# CurrentS_2.net
KiCad netlist of a schematic drawn in Altium Designer
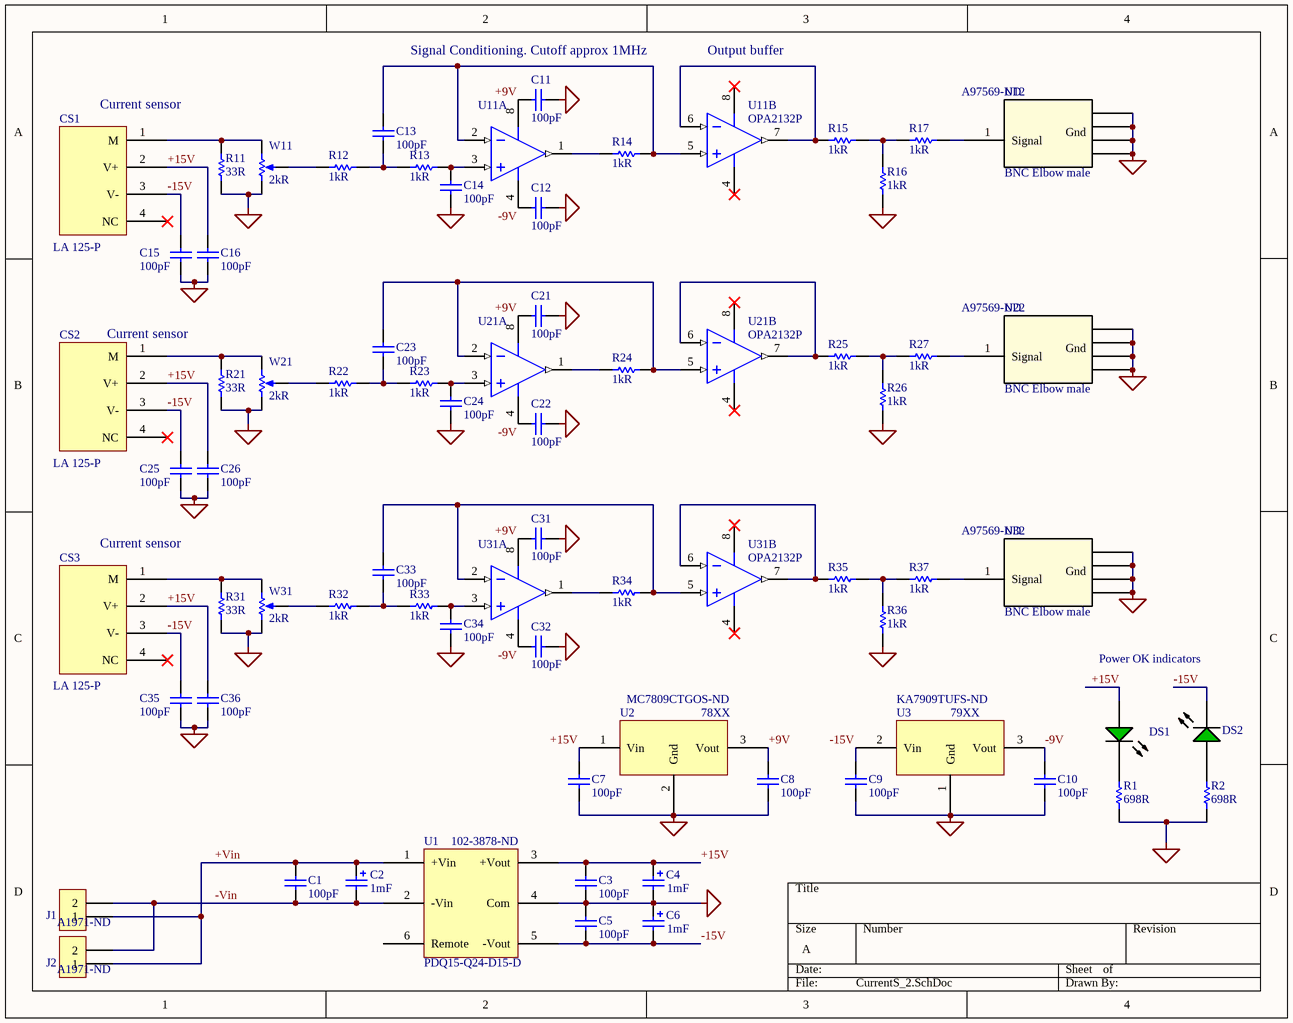
[diagram p0: CurrentS_2.SchDoc]

(export (version "E")
  (design (tool "Eeschema 10.0.6"))
  (components
    (comp (ref "C1")
      (value "C3216C0G2J101J060AA")
      (footprint "C1206")
      (fields
        (field (name "MANUFACTURER") "TDK")
        (field (name "TOLERANCE") "5%")
        (field (name "VOLTAGE") "630V")
        (field (name "CAPACITANCE") "100pF")
      )
      (libsource (lib "KyleCustomModels") (part "C3216C0G2J101J060AA"))
    )
    (comp (ref "C2")
      (value "ESMG500ELL102MK25S")
      (footprint "CAP.2/.5")
      (description "CAP ALUM 1000UF 20% 50V RADIAL")
      (fields
        (field (name "MANUFACTURER") "United Chemi-Con")
        (field (name "TOLERANCE") "20%")
        (field (name "CAPACITANCE") "1mF")
      )
      (libsource (lib "KyleCustomModels") (part "ESMG500ELL102MK25S"))
    )
    (comp (ref "C3")
      (value "C3216C0G2J101J060AA")
      (footprint "C1206")
      (fields
        (field (name "MANUFACTURER") "TDK")
        (field (name "TOLERANCE") "5%")
        (field (name "VOLTAGE") "630V")
        (field (name "CAPACITANCE") "100pF")
      )
      (libsource (lib "KyleCustomModels") (part "C3216C0G2J101J060AA"))
    )
    (comp (ref "C4")
      (value "ESMG500ELL102MK25S")
      (footprint "CAP.2/.5")
      (description "CAP ALUM 1000UF 20% 50V RADIAL")
      (fields
        (field (name "MANUFACTURER") "United Chemi-Con")
        (field (name "TOLERANCE") "20%")
        (field (name "CAPACITANCE") "1mF")
      )
      (libsource (lib "KyleCustomModels") (part "ESMG500ELL102MK25S"))
    )
    (comp (ref "C5")
      (value "C3216C0G2J101J060AA")
      (footprint "C1206")
      (fields
        (field (name "MANUFACTURER") "TDK")
        (field (name "TOLERANCE") "5%")
        (field (name "VOLTAGE") "630V")
        (field (name "CAPACITANCE") "100pF")
      )
      (libsource (lib "KyleCustomModels") (part "C3216C0G2J101J060AA"))
    )
    (comp (ref "C6")
      (value "ESMG500ELL102MK25S")
      (footprint "CAP.2/.5")
      (description "CAP ALUM 1000UF 20% 50V RADIAL")
      (fields
        (field (name "MANUFACTURER") "United Chemi-Con")
        (field (name "TOLERANCE") "20%")
        (field (name "CAPACITANCE") "1mF")
      )
      (libsource (lib "KyleCustomModels") (part "ESMG500ELL102MK25S"))
    )
    (comp (ref "C7")
      (value "C3216C0G2J101J060AA")
      (footprint "C1206")
      (fields
        (field (name "MANUFACTURER") "TDK")
        (field (name "TOLERANCE") "5%")
        (field (name "VOLTAGE") "630V")
        (field (name "CAPACITANCE") "100pF")
      )
      (libsource (lib "KyleCustomModels") (part "C3216C0G2J101J060AA"))
    )
    (comp (ref "C8")
      (value "C3216C0G2J101J060AA")
      (footprint "C1206")
      (fields
        (field (name "MANUFACTURER") "TDK")
        (field (name "TOLERANCE") "5%")
        (field (name "VOLTAGE") "630V")
        (field (name "CAPACITANCE") "100pF")
      )
      (libsource (lib "KyleCustomModels") (part "C3216C0G2J101J060AA"))
    )
    (comp (ref "C9")
      (value "C3216C0G2J101J060AA")
      (footprint "C1206")
      (fields
        (field (name "MANUFACTURER") "TDK")
        (field (name "TOLERANCE") "5%")
        (field (name "VOLTAGE") "630V")
        (field (name "CAPACITANCE") "100pF")
      )
      (libsource (lib "KyleCustomModels") (part "C3216C0G2J101J060AA"))
    )
    (comp (ref "C10")
      (value "C3216C0G2J101J060AA")
      (footprint "C1206")
      (fields
        (field (name "MANUFACTURER") "TDK")
        (field (name "TOLERANCE") "5%")
        (field (name "VOLTAGE") "630V")
        (field (name "CAPACITANCE") "100pF")
      )
      (libsource (lib "KyleCustomModels") (part "C3216C0G2J101J060AA"))
    )
    (comp (ref "C11")
      (value "C3216C0G2J101J060AA")
      (footprint "C1206")
      (fields
        (field (name "MANUFACTURER") "TDK")
        (field (name "TOLERANCE") "5%")
        (field (name "VOLTAGE") "630V")
        (field (name "CAPACITANCE") "100pF")
      )
      (libsource (lib "KyleCustomModels") (part "C3216C0G2J101J060AA"))
    )
    (comp (ref "C12")
      (value "C3216C0G2J101J060AA")
      (footprint "C1206")
      (fields
        (field (name "MANUFACTURER") "TDK")
        (field (name "TOLERANCE") "5%")
        (field (name "VOLTAGE") "630V")
        (field (name "CAPACITANCE") "100pF")
      )
      (libsource (lib "KyleCustomModels") (part "C3216C0G2J101J060AA"))
    )
    (comp (ref "C13")
      (value "C3216C0G2J101J060AA")
      (footprint "C1206")
      (fields
        (field (name "MANUFACTURER") "TDK")
        (field (name "TOLERANCE") "5%")
        (field (name "VOLTAGE") "630V")
        (field (name "CAPACITANCE") "100pF")
      )
      (libsource (lib "KyleCustomModels") (part "C3216C0G2J101J060AA"))
    )
    (comp (ref "C14")
      (value "C3216C0G2J101J060AA")
      (footprint "C1206")
      (fields
        (field (name "MANUFACTURER") "TDK")
        (field (name "TOLERANCE") "5%")
        (field (name "VOLTAGE") "630V")
        (field (name "CAPACITANCE") "100pF")
      )
      (libsource (lib "KyleCustomModels") (part "C3216C0G2J101J060AA"))
    )
    (comp (ref "C15")
      (value "C3216C0G2J101J060AA")
      (footprint "C1206")
      (fields
        (field (name "MANUFACTURER") "TDK")
        (field (name "TOLERANCE") "5%")
        (field (name "VOLTAGE") "630V")
        (field (name "CAPACITANCE") "100pF")
      )
      (libsource (lib "KyleCustomModels") (part "C3216C0G2J101J060AA"))
    )
    (comp (ref "C16")
      (value "C3216C0G2J101J060AA")
      (footprint "C1206")
      (fields
        (field (name "MANUFACTURER") "TDK")
        (field (name "TOLERANCE") "5%")
        (field (name "VOLTAGE") "630V")
        (field (name "CAPACITANCE") "100pF")
      )
      (libsource (lib "KyleCustomModels") (part "C3216C0G2J101J060AA"))
    )
    (comp (ref "C21")
      (value "C3216C0G2J101J060AA")
      (footprint "C1206")
      (fields
        (field (name "MANUFACTURER") "TDK")
        (field (name "TOLERANCE") "5%")
        (field (name "VOLTAGE") "630V")
        (field (name "CAPACITANCE") "100pF")
      )
      (libsource (lib "KyleCustomModels") (part "C3216C0G2J101J060AA"))
    )
    (comp (ref "C22")
      (value "C3216C0G2J101J060AA")
      (footprint "C1206")
      (fields
        (field (name "MANUFACTURER") "TDK")
        (field (name "TOLERANCE") "5%")
        (field (name "VOLTAGE") "630V")
        (field (name "CAPACITANCE") "100pF")
      )
      (libsource (lib "KyleCustomModels") (part "C3216C0G2J101J060AA"))
    )
    (comp (ref "C23")
      (value "C3216C0G2J101J060AA")
      (footprint "C1206")
      (fields
        (field (name "MANUFACTURER") "TDK")
        (field (name "TOLERANCE") "5%")
        (field (name "VOLTAGE") "630V")
        (field (name "CAPACITANCE") "100pF")
      )
      (libsource (lib "KyleCustomModels") (part "C3216C0G2J101J060AA"))
    )
    (comp (ref "C24")
      (value "C3216C0G2J101J060AA")
      (footprint "C1206")
      (fields
        (field (name "MANUFACTURER") "TDK")
        (field (name "TOLERANCE") "5%")
        (field (name "VOLTAGE") "630V")
        (field (name "CAPACITANCE") "100pF")
      )
      (libsource (lib "KyleCustomModels") (part "C3216C0G2J101J060AA"))
    )
    (comp (ref "C25")
      (value "C3216C0G2J101J060AA")
      (footprint "C1206")
      (fields
        (field (name "MANUFACTURER") "TDK")
        (field (name "TOLERANCE") "5%")
        (field (name "VOLTAGE") "630V")
        (field (name "CAPACITANCE") "100pF")
      )
      (libsource (lib "KyleCustomModels") (part "C3216C0G2J101J060AA"))
    )
    (comp (ref "C26")
      (value "C3216C0G2J101J060AA")
      (footprint "C1206")
      (fields
        (field (name "MANUFACTURER") "TDK")
        (field (name "TOLERANCE") "5%")
        (field (name "VOLTAGE") "630V")
        (field (name "CAPACITANCE") "100pF")
      )
      (libsource (lib "KyleCustomModels") (part "C3216C0G2J101J060AA"))
    )
    (comp (ref "C31")
      (value "C3216C0G2J101J060AA")
      (footprint "C1206")
      (fields
        (field (name "MANUFACTURER") "TDK")
        (field (name "TOLERANCE") "5%")
        (field (name "VOLTAGE") "630V")
        (field (name "CAPACITANCE") "100pF")
      )
      (libsource (lib "KyleCustomModels") (part "C3216C0G2J101J060AA"))
    )
    (comp (ref "C32")
      (value "C3216C0G2J101J060AA")
      (footprint "C1206")
      (fields
        (field (name "MANUFACTURER") "TDK")
        (field (name "TOLERANCE") "5%")
        (field (name "VOLTAGE") "630V")
        (field (name "CAPACITANCE") "100pF")
      )
      (libsource (lib "KyleCustomModels") (part "C3216C0G2J101J060AA"))
    )
    (comp (ref "C33")
      (value "C3216C0G2J101J060AA")
      (footprint "C1206")
      (fields
        (field (name "MANUFACTURER") "TDK")
        (field (name "TOLERANCE") "5%")
        (field (name "VOLTAGE") "630V")
        (field (name "CAPACITANCE") "100pF")
      )
      (libsource (lib "KyleCustomModels") (part "C3216C0G2J101J060AA"))
    )
    (comp (ref "C34")
      (value "C3216C0G2J101J060AA")
      (footprint "C1206")
      (fields
        (field (name "MANUFACTURER") "TDK")
        (field (name "TOLERANCE") "5%")
        (field (name "VOLTAGE") "630V")
        (field (name "CAPACITANCE") "100pF")
      )
      (libsource (lib "KyleCustomModels") (part "C3216C0G2J101J060AA"))
    )
    (comp (ref "C35")
      (value "C3216C0G2J101J060AA")
      (footprint "C1206")
      (fields
        (field (name "MANUFACTURER") "TDK")
        (field (name "TOLERANCE") "5%")
        (field (name "VOLTAGE") "630V")
        (field (name "CAPACITANCE") "100pF")
      )
      (libsource (lib "KyleCustomModels") (part "C3216C0G2J101J060AA"))
    )
    (comp (ref "C36")
      (value "C3216C0G2J101J060AA")
      (footprint "C1206")
      (fields
        (field (name "MANUFACTURER") "TDK")
        (field (name "TOLERANCE") "5%")
        (field (name "VOLTAGE") "630V")
        (field (name "CAPACITANCE") "100pF")
      )
      (libsource (lib "KyleCustomModels") (part "C3216C0G2J101J060AA"))
    )
    (comp (ref "CS1")
      (value "LA 125-P")
      (footprint "LA 125-P")
      (description "Hall-effect current transducer from LEM")
      (fields (field (name "MANUFACTURER") "LEM") (field (name "MANUFACTURER PART NUMBER") "LA125-P"))
      (libsource (lib "KyleCustomModels") (part "LA 125-P"))
    )
    (comp (ref "CS2")
      (value "LA 125-P")
      (footprint "LA 125-P")
      (description "Hall-effect current transducer from LEM")
      (fields (field (name "MANUFACTURER") "LEM") (field (name "MANUFACTURER PART NUMBER") "LA125-P"))
      (libsource (lib "KyleCustomModels") (part "LA 125-P"))
    )
    (comp (ref "CS3")
      (value "LA 125-P")
      (footprint "LA 125-P")
      (description "Hall-effect current transducer from LEM")
      (fields (field (name "MANUFACTURER") "LEM") (field (name "MANUFACTURER PART NUMBER") "LA125-P"))
      (libsource (lib "KyleCustomModels") (part "LA 125-P"))
    )
    (comp (ref "DS1")
      (value "SML-LXT0805GW-TR")
      (footprint "LUMX-SML-LXT0805_V")
      (description "LED, GREEN, 565 nm, 2 V, -25 to 80 degC, 2-Pin SMD, RoHS, Tape and Reel")
      (libsource (lib "Altium Content Vault") (part "LED-GREEN-AK-2"))
    )
    (comp (ref "DS2")
      (value "SML-LXT0805GW-TR")
      (footprint "LUMX-SML-LXT0805_V")
      (description "LED, GREEN, 565 nm, 2 V, -25 to 80 degC, 2-Pin SMD, RoHS, Tape and Reel")
      (libsource (lib "Altium Content Vault") (part "LED-GREEN-AK-2"))
    )
    (comp (ref "J1")
      (value "CON2")
      (footprint "3100-8-102-01")
      (description "Connector")
      (fields
        (field (name "MANUFACTURER") "TE Connectivity")
        (field (name "MANUFACTURER PART NUMBER") "640445-2")
        (field (name "SUPPLIER PART NUMBER 1") "A1971-ND")
      )
      (libsource (lib "ERL_Components") (part "CON2"))
    )
    (comp (ref "J2")
      (value "CON2")
      (footprint "3100-8-102-01")
      (description "Connector")
      (fields
        (field (name "MANUFACTURER") "TE Connectivity")
        (field (name "MANUFACTURER PART NUMBER") "640445-2")
        (field (name "SUPPLIER PART NUMBER 1") "A1971-ND")
      )
      (libsource (lib "ERL_Components") (part "CON2"))
    )
    (comp (ref "R1")
      (value "RC0805FR-07698RL")
      (footprint "R0805")
      (description "RES SMD 698 OHM 1% 1/8W 0805")
      (fields
        (field (name "MANUFACTURER") "Yageo")
        (field (name "TOLERANCE") "1%")
        (field (name "RESISTANCE") "698R")
      )
      (libsource (lib "KyleCustomModels") (part "RC0805FR-07698RL"))
    )
    (comp (ref "R2")
      (value "RC0805FR-07698RL")
      (footprint "R0805")
      (description "RES SMD 698 OHM 1% 1/8W 0805")
      (fields
        (field (name "MANUFACTURER") "Yageo")
        (field (name "TOLERANCE") "1%")
        (field (name "RESISTANCE") "698R")
      )
      (libsource (lib "KyleCustomModels") (part "RC0805FR-07698RL"))
    )
    (comp (ref "R11")
      (value "RC0805JR-0733RL")
      (footprint "R0805")
      (fields
        (field (name "MANUFACTURER") "Yageo")
        (field (name "TOLERANCE") "5%")
        (field (name "RESISTANCE") "33R")
      )
      (libsource (lib "KyleCustomModels") (part "RC0805JR-0733RL"))
    )
    (comp (ref "R12")
      (value "RC0805FR-071KL")
      (footprint "R0805")
      (description "RES SMD 1K OHM 1% 1/8W 0805")
      (fields
        (field (name "MANUFACTURER") "Yageo")
        (field (name "TOLERANCE") "1%")
        (field (name "RESISTANCE") "1kR")
      )
      (libsource (lib "KyleCustomModels") (part "RC0805FR-071KL"))
    )
    (comp (ref "R13")
      (value "RC0805FR-071KL")
      (footprint "R0805")
      (description "RES SMD 1K OHM 1% 1/8W 0805")
      (fields
        (field (name "MANUFACTURER") "Yageo")
        (field (name "TOLERANCE") "1%")
        (field (name "RESISTANCE") "1kR")
      )
      (libsource (lib "KyleCustomModels") (part "RC0805FR-071KL"))
    )
    (comp (ref "R14")
      (value "RC0805FR-071KL")
      (footprint "R0805")
      (description "RES SMD 1K OHM 1% 1/8W 0805")
      (fields
        (field (name "MANUFACTURER") "Yageo")
        (field (name "TOLERANCE") "1%")
        (field (name "RESISTANCE") "1kR")
      )
      (libsource (lib "KyleCustomModels") (part "RC0805FR-071KL"))
    )
    (comp (ref "R15")
      (value "RC0805FR-071KL")
      (footprint "R0805")
      (description "RES SMD 1K OHM 1% 1/8W 0805")
      (fields
        (field (name "MANUFACTURER") "Yageo")
        (field (name "TOLERANCE") "1%")
        (field (name "RESISTANCE") "1kR")
      )
      (libsource (lib "KyleCustomModels") (part "RC0805FR-071KL"))
    )
    (comp (ref "R16")
      (value "RC0805FR-071KL")
      (footprint "R0805")
      (description "RES SMD 1K OHM 1% 1/8W 0805")
      (fields
        (field (name "MANUFACTURER") "Yageo")
        (field (name "TOLERANCE") "1%")
        (field (name "RESISTANCE") "1kR")
      )
      (libsource (lib "KyleCustomModels") (part "RC0805FR-071KL"))
    )
    (comp (ref "R17")
      (value "RC0805FR-071KL")
      (footprint "R0805")
      (description "RES SMD 1K OHM 1% 1/8W 0805")
      (fields
        (field (name "MANUFACTURER") "Yageo")
        (field (name "TOLERANCE") "1%")
        (field (name "RESISTANCE") "1kR")
      )
      (libsource (lib "KyleCustomModels") (part "RC0805FR-071KL"))
    )
    (comp (ref "R21")
      (value "RC0805JR-0733RL")
      (footprint "R0805")
      (fields
        (field (name "MANUFACTURER") "Yageo")
        (field (name "TOLERANCE") "5%")
        (field (name "RESISTANCE") "33R")
      )
      (libsource (lib "KyleCustomModels") (part "RC0805JR-0733RL"))
    )
    (comp (ref "R22")
      (value "RC0805FR-071KL")
      (footprint "R0805")
      (description "RES SMD 1K OHM 1% 1/8W 0805")
      (fields
        (field (name "MANUFACTURER") "Yageo")
        (field (name "TOLERANCE") "1%")
        (field (name "RESISTANCE") "1kR")
      )
      (libsource (lib "KyleCustomModels") (part "RC0805FR-071KL"))
    )
    (comp (ref "R23")
      (value "RC0805FR-071KL")
      (footprint "R0805")
      (description "RES SMD 1K OHM 1% 1/8W 0805")
      (fields
        (field (name "MANUFACTURER") "Yageo")
        (field (name "TOLERANCE") "1%")
        (field (name "RESISTANCE") "1kR")
      )
      (libsource (lib "KyleCustomModels") (part "RC0805FR-071KL"))
    )
    (comp (ref "R24")
      (value "RC0805FR-071KL")
      (footprint "R0805")
      (description "RES SMD 1K OHM 1% 1/8W 0805")
      (fields
        (field (name "MANUFACTURER") "Yageo")
        (field (name "TOLERANCE") "1%")
        (field (name "RESISTANCE") "1kR")
      )
      (libsource (lib "KyleCustomModels") (part "RC0805FR-071KL"))
    )
    (comp (ref "R25")
      (value "RC0805FR-071KL")
      (footprint "R0805")
      (description "RES SMD 1K OHM 1% 1/8W 0805")
      (fields
        (field (name "MANUFACTURER") "Yageo")
        (field (name "TOLERANCE") "1%")
        (field (name "RESISTANCE") "1kR")
      )
      (libsource (lib "KyleCustomModels") (part "RC0805FR-071KL"))
    )
    (comp (ref "R26")
      (value "RC0805FR-071KL")
      (footprint "R0805")
      (description "RES SMD 1K OHM 1% 1/8W 0805")
      (fields
        (field (name "MANUFACTURER") "Yageo")
        (field (name "TOLERANCE") "1%")
        (field (name "RESISTANCE") "1kR")
      )
      (libsource (lib "KyleCustomModels") (part "RC0805FR-071KL"))
    )
    (comp (ref "R27")
      (value "RC0805FR-071KL")
      (footprint "R0805")
      (description "RES SMD 1K OHM 1% 1/8W 0805")
      (fields
        (field (name "MANUFACTURER") "Yageo")
        (field (name "TOLERANCE") "1%")
        (field (name "RESISTANCE") "1kR")
      )
      (libsource (lib "KyleCustomModels") (part "RC0805FR-071KL"))
    )
    (comp (ref "R31")
      (value "RC0805JR-0733RL")
      (footprint "R0805")
      (fields
        (field (name "MANUFACTURER") "Yageo")
        (field (name "TOLERANCE") "5%")
        (field (name "RESISTANCE") "33R")
      )
      (libsource (lib "KyleCustomModels") (part "RC0805JR-0733RL"))
    )
    (comp (ref "R32")
      (value "RC0805FR-071KL")
      (footprint "R0805")
      (description "RES SMD 1K OHM 1% 1/8W 0805")
      (fields
        (field (name "MANUFACTURER") "Yageo")
        (field (name "TOLERANCE") "1%")
        (field (name "RESISTANCE") "1kR")
      )
      (libsource (lib "KyleCustomModels") (part "RC0805FR-071KL"))
    )
    (comp (ref "R33")
      (value "RC0805FR-071KL")
      (footprint "R0805")
      (description "RES SMD 1K OHM 1% 1/8W 0805")
      (fields
        (field (name "MANUFACTURER") "Yageo")
        (field (name "TOLERANCE") "1%")
        (field (name "RESISTANCE") "1kR")
      )
      (libsource (lib "KyleCustomModels") (part "RC0805FR-071KL"))
    )
    (comp (ref "R34")
      (value "RC0805FR-071KL")
      (footprint "R0805")
      (description "RES SMD 1K OHM 1% 1/8W 0805")
      (fields
        (field (name "MANUFACTURER") "Yageo")
        (field (name "TOLERANCE") "1%")
        (field (name "RESISTANCE") "1kR")
      )
      (libsource (lib "KyleCustomModels") (part "RC0805FR-071KL"))
    )
    (comp (ref "R35")
      (value "RC0805FR-071KL")
      (footprint "R0805")
      (description "RES SMD 1K OHM 1% 1/8W 0805")
      (fields
        (field (name "MANUFACTURER") "Yageo")
        (field (name "TOLERANCE") "1%")
        (field (name "RESISTANCE") "1kR")
      )
      (libsource (lib "KyleCustomModels") (part "RC0805FR-071KL"))
    )
    (comp (ref "R36")
      (value "RC0805FR-071KL")
      (footprint "R0805")
      (description "RES SMD 1K OHM 1% 1/8W 0805")
      (fields
        (field (name "MANUFACTURER") "Yageo")
        (field (name "TOLERANCE") "1%")
        (field (name "RESISTANCE") "1kR")
      )
      (libsource (lib "KyleCustomModels") (part "RC0805FR-071KL"))
    )
    (comp (ref "R37")
      (value "RC0805FR-071KL")
      (footprint "R0805")
      (description "RES SMD 1K OHM 1% 1/8W 0805")
      (fields
        (field (name "MANUFACTURER") "Yageo")
        (field (name "TOLERANCE") "1%")
        (field (name "RESISTANCE") "1kR")
      )
      (libsource (lib "KyleCustomModels") (part "RC0805FR-071KL"))
    )
    (comp (ref "U1")
      (value "PDQ15-Q24-D15-D")
      (footprint "PDQ15-Q24-D15-D")
      (description "Isolated DC/DC Converters 15W 9-36Vin +/-15V +/-500mA Iso Reg DIP")
      (fields (field (name "SUPPLIER PART NUMBER 1") "102-3878-ND"))
      (libsource (lib "KyleCustomModels") (part "PDQ15-Q24-D15-D"))
    )
    (comp (ref "U2")
      (value "78XX")
      (footprint "TO-220")
      (description "IC REG LINEAR 9V 1A TO220AB")
      (fields
        (field (name "MANUFACTURER") "ON Semiconductor")
        (field (name "MANUFACTURER PART NUMBER") "MC7809CTG")
        (field (name "SUPPLIER PART NUMBER 1") "MC7809CTGOS-ND")
      )
      (libsource (lib "KyleCustomModels") (part "78XX"))
    )
    (comp (ref "U3")
      (value "79XX")
      (footprint "TO-220")
      (description "IC REG LINEAR -9V 1A TO220-3")
      (fields
        (field (name "MANUFACTURER") "ON Semiconductor / Fairchild")
        (field (name "MANUFACTURER PART NUMBER") "KA7909TU")
        (field (name "SUPPLIER PART NUMBER 1") "KA7909TUFS-ND")
      )
      (libsource (lib "KyleCustomModels") (part "79XX"))
    )
    (comp (ref "U11")
      (value "OPA2132P")
      (footprint "P0008A")
      (fields (field (name "MANUFACTURER") "Texas Instruments"))
      (libsource (lib "Altium Content Vault") (part "TI-OPA-8_2"))
    )
    (comp (ref "U12")
      (value "BNC Elbow male")
      (footprint "5-1814400-1")
      (description "BNC Low Profile Elbow Connector")
      (fields
        (field (name "MANUFACTURER_PART_NUMBER") "5-1634513-1")
        (field (name "MANUFACTURER") "TE Connectivity")
        (field (name "SUPPLIER PART NUMBER 1") "A97569-ND")
        (field (name "COPYRIGHT") "Copyright (C) 2015 Accelerated Designs. All rights reserved")
      )
      (libsource (lib "ERL_Components") (part "BNC Elbow male"))
    )
    (comp (ref "U21")
      (value "OPA2132P")
      (footprint "P0008A")
      (fields (field (name "MANUFACTURER") "Texas Instruments"))
      (libsource (lib "Altium Content Vault") (part "TI-OPA-8_2"))
    )
    (comp (ref "U22")
      (value "BNC Elbow male")
      (footprint "5-1814400-1")
      (description "BNC Low Profile Elbow Connector")
      (fields
        (field (name "MANUFACTURER_PART_NUMBER") "5-1634513-1")
        (field (name "MANUFACTURER") "TE Connectivity")
        (field (name "SUPPLIER PART NUMBER 1") "A97569-ND")
        (field (name "COPYRIGHT") "Copyright (C) 2015 Accelerated Designs. All rights reserved")
      )
      (libsource (lib "ERL_Components") (part "BNC Elbow male"))
    )
    (comp (ref "U31")
      (value "OPA2132P")
      (footprint "P0008A")
      (fields (field (name "MANUFACTURER") "Texas Instruments"))
      (libsource (lib "Altium Content Vault") (part "TI-OPA-8_2"))
    )
    (comp (ref "U32")
      (value "BNC Elbow male")
      (footprint "5-1814400-1")
      (description "BNC Low Profile Elbow Connector")
      (fields
        (field (name "MANUFACTURER_PART_NUMBER") "5-1634513-1")
        (field (name "MANUFACTURER") "TE Connectivity")
        (field (name "SUPPLIER PART NUMBER 1") "A97569-ND")
        (field (name "COPYRIGHT") "Copyright (C) 2015 Accelerated Designs. All rights reserved")
      )
      (libsource (lib "ERL_Components") (part "BNC Elbow male"))
    )
    (comp (ref "W11")
      (value "PV36W202C01B00")
      (footprint "VR5")
      (description "TRIMMER 2K OHM 0.5W TH")
      (fields
        (field (name "MANUFACTURER") "Bourns")
        (field (name "TOLERANCE") "10%")
        (field (name "RESISTANCE") "2kR")
      )
      (libsource (lib "KyleCustomModels") (part "PV36W202C01B00"))
    )
    (comp (ref "W21")
      (value "PV36W202C01B00")
      (footprint "VR5")
      (description "TRIMMER 2K OHM 0.5W TH")
      (fields
        (field (name "MANUFACTURER") "Bourns")
        (field (name "TOLERANCE") "10%")
        (field (name "RESISTANCE") "2kR")
      )
      (libsource (lib "KyleCustomModels") (part "PV36W202C01B00"))
    )
    (comp (ref "W31")
      (value "PV36W202C01B00")
      (footprint "VR5")
      (description "TRIMMER 2K OHM 0.5W TH")
      (fields
        (field (name "MANUFACTURER") "Bourns")
        (field (name "TOLERANCE") "10%")
        (field (name "RESISTANCE") "2kR")
      )
      (libsource (lib "KyleCustomModels") (part "PV36W202C01B00"))
    )
  )
  (nets
    (net (code "1") (name "/+9V") (class "Default")
      (node (ref "C11") (pin "1") (pinfunction "1_1") (pintype "passive"))
      (node (ref "C21") (pin "1") (pinfunction "1_1") (pintype "passive"))
      (node (ref "C31") (pin "1") (pinfunction "1_1") (pintype "passive"))
      (node (ref "C8") (pin "2") (pinfunction "2_2") (pintype "passive"))
      (node (ref "U11") (pin "8") (pinfunction "V+_8") (pintype "power_in"))
      (node (ref "U2") (pin "3") (pinfunction "Vout_3") (pintype "passive"))
      (node (ref "U21") (pin "8") (pinfunction "V+_8") (pintype "power_in"))
      (node (ref "U31") (pin "8") (pinfunction "V+_8") (pintype "power_in"))
    )
    (net (code "2") (name "/+15V") (class "Default")
      (node (ref "C16") (pin "2") (pinfunction "2_2") (pintype "passive"))
      (node (ref "C26") (pin "2") (pinfunction "2_2") (pintype "passive"))
      (node (ref "C3") (pin "2") (pinfunction "2_2") (pintype "passive"))
      (node (ref "C36") (pin "2") (pinfunction "2_2") (pintype "passive"))
      (node (ref "C4") (pin "1") (pinfunction "1_1") (pintype "passive"))
      (node (ref "C7") (pin "2") (pinfunction "2_2") (pintype "passive"))
      (node (ref "CS1") (pin "2") (pinfunction "V+_2") (pintype "passive"))
      (node (ref "CS2") (pin "2") (pinfunction "V+_2") (pintype "passive"))
      (node (ref "CS3") (pin "2") (pinfunction "V+_2") (pintype "passive"))
      (node (ref "DS1") (pin "1") (pinfunction "A_1") (pintype "passive"))
      (node (ref "U1") (pin "3") (pinfunction "+Vout_3") (pintype "power_in"))
      (node (ref "U2") (pin "1") (pinfunction "Vin_1") (pintype "passive"))
    )
    (net (code "3") (name "/+Vin") (class "Default")
      (node (ref "C1") (pin "2") (pinfunction "2_2") (pintype "passive"))
      (node (ref "C2") (pin "1") (pinfunction "1_1") (pintype "passive"))
      (node (ref "J1") (pin "1") (pinfunction "1_1") (pintype "passive"))
      (node (ref "J2") (pin "1") (pinfunction "1_1") (pintype "passive"))
      (node (ref "U1") (pin "1") (pinfunction "+Vin_1") (pintype "power_in"))
    )
    (net (code "4") (name "/-9V") (class "Default")
      (node (ref "C10") (pin "2") (pinfunction "2_2") (pintype "passive"))
      (node (ref "C12") (pin "1") (pinfunction "1_1") (pintype "passive"))
      (node (ref "C22") (pin "1") (pinfunction "1_1") (pintype "passive"))
      (node (ref "C32") (pin "1") (pinfunction "1_1") (pintype "passive"))
      (node (ref "U11") (pin "4") (pinfunction "V-_4") (pintype "power_in"))
      (node (ref "U21") (pin "4") (pinfunction "V-_4") (pintype "power_in"))
      (node (ref "U3") (pin "3") (pinfunction "Vout_3") (pintype "passive"))
      (node (ref "U31") (pin "4") (pinfunction "V-_4") (pintype "power_in"))
    )
    (net (code "5") (name "/-15V") (class "Default")
      (node (ref "C15") (pin "2") (pinfunction "2_2") (pintype "passive"))
      (node (ref "C25") (pin "2") (pinfunction "2_2") (pintype "passive"))
      (node (ref "C35") (pin "2") (pinfunction "2_2") (pintype "passive"))
      (node (ref "C5") (pin "1") (pinfunction "1_1") (pintype "passive"))
      (node (ref "C6") (pin "2") (pinfunction "2_2") (pintype "passive"))
      (node (ref "C9") (pin "2") (pinfunction "2_2") (pintype "passive"))
      (node (ref "CS1") (pin "3") (pinfunction "V-_3") (pintype "passive"))
      (node (ref "CS2") (pin "3") (pinfunction "V-_3") (pintype "passive"))
      (node (ref "CS3") (pin "3") (pinfunction "V-_3") (pintype "passive"))
      (node (ref "DS2") (pin "2") (pinfunction "K_2") (pintype "passive"))
      (node (ref "U1") (pin "5") (pinfunction "-Vout_5") (pintype "power_in"))
      (node (ref "U3") (pin "2") (pinfunction "Vin_2") (pintype "passive"))
    )
    (net (code "6") (name "/-Vin") (class "Default")
      (node (ref "C1") (pin "1") (pinfunction "1_1") (pintype "passive"))
      (node (ref "C2") (pin "2") (pinfunction "2_2") (pintype "passive"))
      (node (ref "J1") (pin "2") (pinfunction "2_2") (pintype "passive"))
      (node (ref "J2") (pin "2") (pinfunction "2_2") (pintype "passive"))
      (node (ref "U1") (pin "2") (pinfunction "-Vin_2") (pintype "power_in"))
    )
    (net (code "7") (name "GND") (class "Default")
      (node (ref "C10") (pin "1") (pinfunction "1_1") (pintype "passive"))
      (node (ref "C11") (pin "2") (pinfunction "2_2") (pintype "passive"))
      (node (ref "C12") (pin "2") (pinfunction "2_2") (pintype "passive"))
      (node (ref "C14") (pin "1") (pinfunction "1_1") (pintype "passive"))
      (node (ref "C15") (pin "1") (pinfunction "1_1") (pintype "passive"))
      (node (ref "C16") (pin "1") (pinfunction "1_1") (pintype "passive"))
      (node (ref "C21") (pin "2") (pinfunction "2_2") (pintype "passive"))
      (node (ref "C22") (pin "2") (pinfunction "2_2") (pintype "passive"))
      (node (ref "C24") (pin "1") (pinfunction "1_1") (pintype "passive"))
      (node (ref "C25") (pin "1") (pinfunction "1_1") (pintype "passive"))
      (node (ref "C26") (pin "1") (pinfunction "1_1") (pintype "passive"))
      (node (ref "C3") (pin "1") (pinfunction "1_1") (pintype "passive"))
      (node (ref "C31") (pin "2") (pinfunction "2_2") (pintype "passive"))
      (node (ref "C32") (pin "2") (pinfunction "2_2") (pintype "passive"))
      (node (ref "C34") (pin "1") (pinfunction "1_1") (pintype "passive"))
      (node (ref "C35") (pin "1") (pinfunction "1_1") (pintype "passive"))
      (node (ref "C36") (pin "1") (pinfunction "1_1") (pintype "passive"))
      (node (ref "C4") (pin "2") (pinfunction "2_2") (pintype "passive"))
      (node (ref "C5") (pin "2") (pinfunction "2_2") (pintype "passive"))
      (node (ref "C6") (pin "1") (pinfunction "1_1") (pintype "passive"))
      (node (ref "C7") (pin "1") (pinfunction "1_1") (pintype "passive"))
      (node (ref "C8") (pin "1") (pinfunction "1_1") (pintype "passive"))
      (node (ref "C9") (pin "1") (pinfunction "1_1") (pintype "passive"))
      (node (ref "R1") (pin "1") (pinfunction "1_1") (pintype "passive"))
      (node (ref "R11") (pin "1") (pinfunction "1_1") (pintype "passive"))
      (node (ref "R16") (pin "1") (pinfunction "1_1") (pintype "passive"))
      (node (ref "R2") (pin "1") (pinfunction "1_1") (pintype "passive"))
      (node (ref "R21") (pin "1") (pinfunction "1_1") (pintype "passive"))
      (node (ref "R26") (pin "1") (pinfunction "1_1") (pintype "passive"))
      (node (ref "R31") (pin "1") (pinfunction "1_1") (pintype "passive"))
      (node (ref "R36") (pin "1") (pinfunction "1_1") (pintype "passive"))
      (node (ref "U1") (pin "4") (pinfunction "Com_4") (pintype "power_in"))
      (node (ref "U12") (pin "2") (pinfunction "2_2") (pintype "passive"))
      (node (ref "U12") (pin "3") (pinfunction "3_3") (pintype "passive"))
      (node (ref "U12") (pin "4") (pinfunction "4_4") (pintype "passive"))
      (node (ref "U12") (pin "5") (pinfunction "5_5") (pintype "passive"))
      (node (ref "U2") (pin "2") (pinfunction "Gnd_2") (pintype "passive"))
      (node (ref "U22") (pin "2") (pinfunction "2_2") (pintype "passive"))
      (node (ref "U22") (pin "3") (pinfunction "3_3") (pintype "passive"))
      (node (ref "U22") (pin "4") (pinfunction "4_4") (pintype "passive"))
      (node (ref "U22") (pin "5") (pinfunction "5_5") (pintype "passive"))
      (node (ref "U3") (pin "1") (pinfunction "Gnd_1") (pintype "passive"))
      (node (ref "U32") (pin "2") (pinfunction "2_2") (pintype "passive"))
      (node (ref "U32") (pin "3") (pinfunction "3_3") (pintype "passive"))
      (node (ref "U32") (pin "4") (pinfunction "4_4") (pintype "passive"))
      (node (ref "U32") (pin "5") (pinfunction "5_5") (pintype "passive"))
      (node (ref "W11") (pin "1") (pinfunction "TOP_1") (pintype "passive"))
      (node (ref "W21") (pin "1") (pinfunction "TOP_1") (pintype "passive"))
      (node (ref "W31") (pin "1") (pinfunction "TOP_1") (pintype "passive"))
    )
    (net (code "8") (name "Net-(C13-Pad1)") (class "Default")
      (node (ref "C13") (pin "1") (pinfunction "1_1") (pintype "passive"))
      (node (ref "R12") (pin "2") (pinfunction "2_2") (pintype "passive"))
      (node (ref "R13") (pin "1") (pinfunction "1_1") (pintype "passive"))
    )
    (net (code "9") (name "Net-(C23-Pad1)") (class "Default")
      (node (ref "C23") (pin "1") (pinfunction "1_1") (pintype "passive"))
      (node (ref "R22") (pin "2") (pinfunction "2_2") (pintype "passive"))
      (node (ref "R23") (pin "1") (pinfunction "1_1") (pintype "passive"))
    )
    (net (code "10") (name "Net-(C33-Pad1)") (class "Default")
      (node (ref "C33") (pin "1") (pinfunction "1_1") (pintype "passive"))
      (node (ref "R32") (pin "2") (pinfunction "2_2") (pintype "passive"))
      (node (ref "R33") (pin "1") (pinfunction "1_1") (pintype "passive"))
    )
    (net (code "11") (name "Net-(CS1-M)") (class "Default")
      (node (ref "CS1") (pin "1") (pinfunction "M_1") (pintype "passive"))
      (node (ref "R11") (pin "2") (pinfunction "2_2") (pintype "passive"))
      (node (ref "W11") (pin "3") (pinfunction "TAP_3") (pintype "passive"))
    )
    (net (code "12") (name "Net-(CS2-M)") (class "Default")
      (node (ref "CS2") (pin "1") (pinfunction "M_1") (pintype "passive"))
      (node (ref "R21") (pin "2") (pinfunction "2_2") (pintype "passive"))
      (node (ref "W21") (pin "3") (pinfunction "TAP_3") (pintype "passive"))
    )
    (net (code "13") (name "Net-(CS3-M)") (class "Default")
      (node (ref "CS3") (pin "1") (pinfunction "M_1") (pintype "passive"))
      (node (ref "R31") (pin "2") (pinfunction "2_2") (pintype "passive"))
      (node (ref "W31") (pin "3") (pinfunction "TAP_3") (pintype "passive"))
    )
    (net (code "14") (name "Net-(DS1-K)") (class "Default")
      (node (ref "DS1") (pin "2") (pinfunction "K_2") (pintype "passive"))
      (node (ref "R1") (pin "2") (pinfunction "2_2") (pintype "passive"))
    )
    (net (code "15") (name "Net-(DS2-A)") (class "Default")
      (node (ref "DS2") (pin "1") (pinfunction "A_1") (pintype "passive"))
      (node (ref "R2") (pin "2") (pinfunction "2_2") (pintype "passive"))
    )
    (net (code "16") (name "Net-(R15-Pad2)") (class "Default")
      (node (ref "R15") (pin "2") (pinfunction "2_2") (pintype "passive"))
      (node (ref "R16") (pin "2") (pinfunction "2_2") (pintype "passive"))
      (node (ref "R17") (pin "2") (pinfunction "2_2") (pintype "passive"))
    )
    (net (code "17") (name "Net-(R25-Pad2)") (class "Default")
      (node (ref "R25") (pin "2") (pinfunction "2_2") (pintype "passive"))
      (node (ref "R26") (pin "2") (pinfunction "2_2") (pintype "passive"))
      (node (ref "R27") (pin "2") (pinfunction "2_2") (pintype "passive"))
    )
    (net (code "18") (name "Net-(R35-Pad2)") (class "Default")
      (node (ref "R35") (pin "2") (pinfunction "2_2") (pintype "passive"))
      (node (ref "R36") (pin "2") (pinfunction "2_2") (pintype "passive"))
      (node (ref "R37") (pin "2") (pinfunction "2_2") (pintype "passive"))
    )
    (net (code "19") (name "Net-(U11A-IN_A+)") (class "Default")
      (node (ref "C14") (pin "2") (pinfunction "2_2") (pintype "passive"))
      (node (ref "R13") (pin "2") (pinfunction "2_2") (pintype "passive"))
      (node (ref "U11") (pin "3") (pinfunction "IN_A+_3") (pintype "input"))
    )
    (net (code "20") (name "Net-(U11A-IN_A-)") (class "Default")
      (node (ref "C13") (pin "2") (pinfunction "2_2") (pintype "passive"))
      (node (ref "R14") (pin "2") (pinfunction "2_2") (pintype "passive"))
      (node (ref "U11") (pin "2") (pinfunction "IN_A-_2") (pintype "input"))
      (node (ref "U11") (pin "5") (pinfunction "IN_B+_5") (pintype "input"))
    )
    (net (code "21") (name "Net-(U11A-OUT_A)") (class "Default")
      (node (ref "R14") (pin "1") (pinfunction "1_1") (pintype "passive"))
      (node (ref "U11") (pin "1") (pinfunction "OUT_A_1") (pintype "output"))
    )
    (net (code "22") (name "Net-(U11B-IN_B-)") (class "Default")
      (node (ref "R15") (pin "1") (pinfunction "1_1") (pintype "passive"))
      (node (ref "U11") (pin "6") (pinfunction "IN_B-_6") (pintype "input"))
      (node (ref "U11") (pin "7") (pinfunction "OUT_B_7") (pintype "output"))
    )
    (net (code "23") (name "Net-(U12-Signal)") (class "Default")
      (node (ref "R17") (pin "1") (pinfunction "1_1") (pintype "passive"))
      (node (ref "U12") (pin "1") (pinfunction "Signal_1") (pintype "passive"))
    )
    (net (code "24") (name "Net-(U21A-IN_A+)") (class "Default")
      (node (ref "C24") (pin "2") (pinfunction "2_2") (pintype "passive"))
      (node (ref "R23") (pin "2") (pinfunction "2_2") (pintype "passive"))
      (node (ref "U21") (pin "3") (pinfunction "IN_A+_3") (pintype "input"))
    )
    (net (code "25") (name "Net-(U21A-IN_A-)") (class "Default")
      (node (ref "C23") (pin "2") (pinfunction "2_2") (pintype "passive"))
      (node (ref "R24") (pin "2") (pinfunction "2_2") (pintype "passive"))
      (node (ref "U21") (pin "2") (pinfunction "IN_A-_2") (pintype "input"))
      (node (ref "U21") (pin "5") (pinfunction "IN_B+_5") (pintype "input"))
    )
    (net (code "26") (name "Net-(U21A-OUT_A)") (class "Default")
      (node (ref "R24") (pin "1") (pinfunction "1_1") (pintype "passive"))
      (node (ref "U21") (pin "1") (pinfunction "OUT_A_1") (pintype "output"))
    )
    (net (code "27") (name "Net-(U21B-IN_B-)") (class "Default")
      (node (ref "R25") (pin "1") (pinfunction "1_1") (pintype "passive"))
      (node (ref "U21") (pin "6") (pinfunction "IN_B-_6") (pintype "input"))
      (node (ref "U21") (pin "7") (pinfunction "OUT_B_7") (pintype "output"))
    )
    (net (code "28") (name "Net-(U22-Signal)") (class "Default")
      (node (ref "R27") (pin "1") (pinfunction "1_1") (pintype "passive"))
      (node (ref "U22") (pin "1") (pinfunction "Signal_1") (pintype "passive"))
    )
    (net (code "29") (name "Net-(U31A-IN_A+)") (class "Default")
      (node (ref "C34") (pin "2") (pinfunction "2_2") (pintype "passive"))
      (node (ref "R33") (pin "2") (pinfunction "2_2") (pintype "passive"))
      (node (ref "U31") (pin "3") (pinfunction "IN_A+_3") (pintype "input"))
    )
    (net (code "30") (name "Net-(U31A-IN_A-)") (class "Default")
      (node (ref "C33") (pin "2") (pinfunction "2_2") (pintype "passive"))
      (node (ref "R34") (pin "2") (pinfunction "2_2") (pintype "passive"))
      (node (ref "U31") (pin "2") (pinfunction "IN_A-_2") (pintype "input"))
      (node (ref "U31") (pin "5") (pinfunction "IN_B+_5") (pintype "input"))
    )
    (net (code "31") (name "Net-(U31A-OUT_A)") (class "Default")
      (node (ref "R34") (pin "1") (pinfunction "1_1") (pintype "passive"))
      (node (ref "U31") (pin "1") (pinfunction "OUT_A_1") (pintype "output"))
    )
    (net (code "32") (name "Net-(U31B-IN_B-)") (class "Default")
      (node (ref "R35") (pin "1") (pinfunction "1_1") (pintype "passive"))
      (node (ref "U31") (pin "6") (pinfunction "IN_B-_6") (pintype "input"))
      (node (ref "U31") (pin "7") (pinfunction "OUT_B_7") (pintype "output"))
    )
    (net (code "33") (name "Net-(U32-Signal)") (class "Default")
      (node (ref "R37") (pin "1") (pinfunction "1_1") (pintype "passive"))
      (node (ref "U32") (pin "1") (pinfunction "Signal_1") (pintype "passive"))
    )
    (net (code "34") (name "Net-(W11-BOT)") (class "Default")
      (node (ref "R12") (pin "1") (pinfunction "1_1") (pintype "passive"))
      (node (ref "W11") (pin "2") (pinfunction "BOT_2") (pintype "passive"))
    )
    (net (code "35") (name "Net-(W21-BOT)") (class "Default")
      (node (ref "R22") (pin "1") (pinfunction "1_1") (pintype "passive"))
      (node (ref "W21") (pin "2") (pinfunction "BOT_2") (pintype "passive"))
    )
    (net (code "36") (name "Net-(W31-BOT)") (class "Default")
      (node (ref "R32") (pin "1") (pinfunction "1_1") (pintype "passive"))
      (node (ref "W31") (pin "2") (pinfunction "BOT_2") (pintype "passive"))
    )
    (net (code "37") (name "unconnected-(CS1-NC-Pad4)") (class "Default")
      (node (ref "CS1") (pin "4") (pinfunction "NC_4") (pintype "passive+no_connect"))
    )
    (net (code "38") (name "unconnected-(CS2-NC-Pad4)") (class "Default")
      (node (ref "CS2") (pin "4") (pinfunction "NC_4") (pintype "passive+no_connect"))
    )
    (net (code "39") (name "unconnected-(CS3-NC-Pad4)") (class "Default")
      (node (ref "CS3") (pin "4") (pinfunction "NC_4") (pintype "passive+no_connect"))
    )
    (net (code "40") (name "unconnected-(U1-Remote-Pad6)") (class "Default")
      (node (ref "U1") (pin "6") (pinfunction "Remote_6") (pintype "passive"))
    )
    (net (code "41") (name "unconnected-(U11B-V+-Pad8)") (class "Default")
      (node (ref "U11") (pin "8") (pinfunction "V+_8") (pintype "power_in+no_connect"))
    )
    (net (code "42") (name "unconnected-(U11B-V--Pad4)") (class "Default")
      (node (ref "U11") (pin "4") (pinfunction "V-_4") (pintype "power_in+no_connect"))
    )
    (net (code "43") (name "unconnected-(U21B-V+-Pad8)") (class "Default")
      (node (ref "U21") (pin "8") (pinfunction "V+_8") (pintype "power_in+no_connect"))
    )
    (net (code "44") (name "unconnected-(U21B-V--Pad4)") (class "Default")
      (node (ref "U21") (pin "4") (pinfunction "V-_4") (pintype "power_in+no_connect"))
    )
    (net (code "45") (name "unconnected-(U31B-V+-Pad8)") (class "Default")
      (node (ref "U31") (pin "8") (pinfunction "V+_8") (pintype "power_in+no_connect"))
    )
    (net (code "46") (name "unconnected-(U31B-V--Pad4)") (class "Default")
      (node (ref "U31") (pin "4") (pinfunction "V-_4") (pintype "power_in+no_connect"))
    )
  )
)
